# ESOL01_-_Sol_Pump.net
KiCad netlist of a schematic drawn in EAGLE
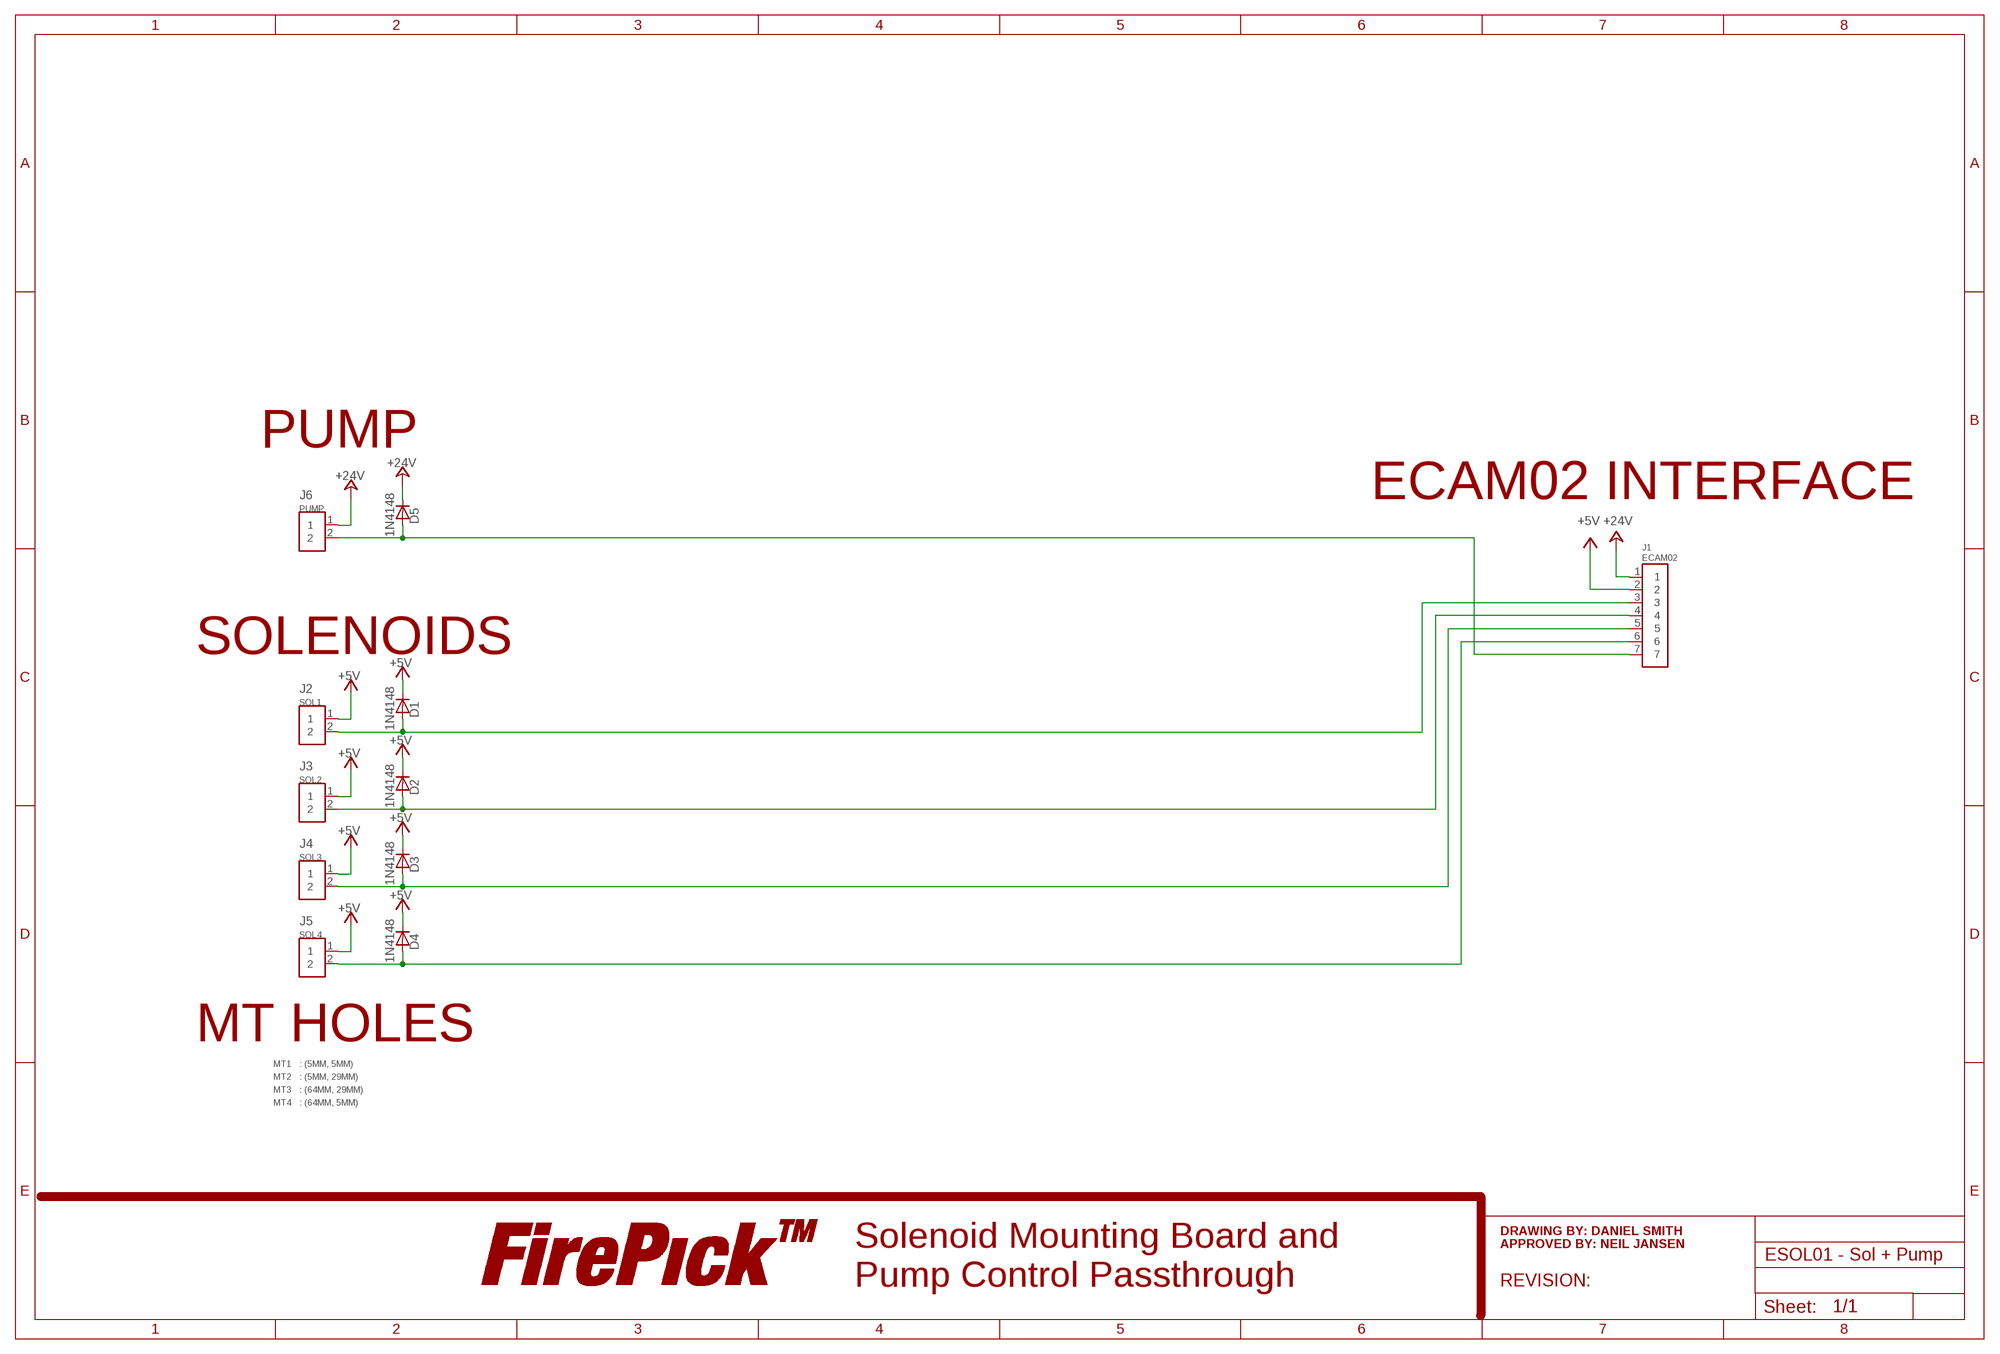
[diagram p0: schematic, sheet 1]

(export (version "E")
  (design (tool "Eeschema 10.0.6"))
  (components
    (comp (ref "D1")
      (value "1N4148")
      (footprint "eagle-import:SOD-323")
      (libsource (lib "eagle-import") (part "CPL-DIO-1N4148SOD-323"))
    )
    (comp (ref "D2")
      (value "1N4148")
      (footprint "eagle-import:SOD-323")
      (libsource (lib "eagle-import") (part "CPL-DIO-1N4148SOD-323"))
    )
    (comp (ref "D3")
      (value "1N4148")
      (footprint "eagle-import:SOD-323")
      (libsource (lib "eagle-import") (part "CPL-DIO-1N4148SOD-323"))
    )
    (comp (ref "D4")
      (value "1N4148")
      (footprint "eagle-import:SOD-323")
      (libsource (lib "eagle-import") (part "CPL-DIO-1N4148SOD-323"))
    )
    (comp (ref "D5")
      (value "1N4148")
      (footprint "eagle-import:SOD-323")
      (libsource (lib "eagle-import") (part "CPL-DIO-1N4148SOD-323"))
    )
    (comp (ref "J1")
      (value "ECAM02")
      (footprint "eagle-import:CON-JST-PH-2.0MM-7P-SMT-VRT")
      (libsource (lib "eagle-import") (part "CPL-CON-JST-2.0MM-7P-M-SMT-VRT"))
    )
    (comp (ref "J2")
      (value "SOL1")
      (footprint "eagle-import:HOLEX2")
      (libsource (lib "eagle-import") (part "HOLEX2"))
    )
    (comp (ref "J3")
      (value "SOL2")
      (footprint "eagle-import:HOLEX2")
      (libsource (lib "eagle-import") (part "HOLEX2"))
    )
    (comp (ref "J4")
      (value "SOL3")
      (footprint "eagle-import:HOLEX2")
      (libsource (lib "eagle-import") (part "HOLEX2"))
    )
    (comp (ref "J5")
      (value "SOL4")
      (footprint "eagle-import:HOLEX2")
      (libsource (lib "eagle-import") (part "HOLEX2"))
    )
    (comp (ref "J6")
      (value "PUMP")
      (footprint "eagle-import:CON-JST-PH-2.0MM-2P-SMT-VRT")
      (libsource (lib "eagle-import") (part "CPL-CON-JST-2.0MM-2P-M-SMT-VRT"))
    )
    (comp (ref "LOGO2")
      (value "LOGO-FIREPICKLARGE")
      (footprint "eagle-import:LOGO-FIREPICK")
      (libsource (lib "eagle-import") (part "LOGO-FIREPICKLARGE"))
    )
    (comp (ref "MT1")
      (value ": (5MM, 5MM)")
      (footprint "eagle-import:MTHOLE(M3)")
      (libsource (lib "eagle-import") (part "MTHOLE(M3)"))
    )
    (comp (ref "MT2")
      (value ": (5MM, 29MM)")
      (footprint "eagle-import:MTHOLE(M3)")
      (libsource (lib "eagle-import") (part "MTHOLE(M3)"))
    )
    (comp (ref "MT3")
      (value ": (64MM, 29MM)")
      (footprint "eagle-import:MTHOLE(M3)")
      (libsource (lib "eagle-import") (part "MTHOLE(M3)"))
    )
    (comp (ref "MT4")
      (value ": (64MM, 5MM)")
      (footprint "eagle-import:MTHOLE(M3)")
      (libsource (lib "eagle-import") (part "MTHOLE(M3)"))
    )
  )
  (nets
    (net (code "1") (name "+5V") (class "Default")
      (node (ref "D1") (pin "NEG") (pinfunction "C_NEG") (pintype "passive"))
      (node (ref "D2") (pin "NEG") (pinfunction "C_NEG") (pintype "passive"))
      (node (ref "D3") (pin "NEG") (pinfunction "C_NEG") (pintype "passive"))
      (node (ref "D4") (pin "NEG") (pinfunction "C_NEG") (pintype "passive"))
      (node (ref "J1") (pin "2") (pinfunction "2_2") (pintype "bidirectional"))
      (node (ref "J2") (pin "1") (pinfunction "1_1") (pintype "passive"))
      (node (ref "J3") (pin "1") (pinfunction "1_1") (pintype "passive"))
      (node (ref "J4") (pin "1") (pinfunction "1_1") (pintype "passive"))
      (node (ref "J5") (pin "1") (pinfunction "1_1") (pintype "passive"))
    )
    (net (code "2") (name "+24V") (class "Default")
      (node (ref "D5") (pin "NEG") (pinfunction "C_NEG") (pintype "passive"))
      (node (ref "J1") (pin "1") (pinfunction "1_1") (pintype "bidirectional"))
      (node (ref "J6") (pin "1") (pinfunction "1_1") (pintype "passive"))
    )
    (net (code "3") (name "Net-(D1-A)") (class "Default")
      (node (ref "D1") (pin "POS") (pinfunction "A_POS") (pintype "passive"))
      (node (ref "J1") (pin "3") (pinfunction "3_3") (pintype "bidirectional"))
      (node (ref "J2") (pin "2") (pinfunction "2_2") (pintype "passive"))
    )
    (net (code "4") (name "Net-(D2-A)") (class "Default")
      (node (ref "D2") (pin "POS") (pinfunction "A_POS") (pintype "passive"))
      (node (ref "J1") (pin "4") (pinfunction "4_4") (pintype "bidirectional"))
      (node (ref "J3") (pin "2") (pinfunction "2_2") (pintype "passive"))
    )
    (net (code "5") (name "Net-(D3-A)") (class "Default")
      (node (ref "D3") (pin "POS") (pinfunction "A_POS") (pintype "passive"))
      (node (ref "J1") (pin "5") (pinfunction "5_5") (pintype "bidirectional"))
      (node (ref "J4") (pin "2") (pinfunction "2_2") (pintype "passive"))
    )
    (net (code "6") (name "Net-(D4-A)") (class "Default")
      (node (ref "D4") (pin "POS") (pinfunction "A_POS") (pintype "passive"))
      (node (ref "J1") (pin "6") (pinfunction "6_6") (pintype "bidirectional"))
      (node (ref "J5") (pin "2") (pinfunction "2_2") (pintype "passive"))
    )
    (net (code "7") (name "Net-(D5-A)") (class "Default")
      (node (ref "D5") (pin "POS") (pinfunction "A_POS") (pintype "passive"))
      (node (ref "J1") (pin "7") (pinfunction "7_7") (pintype "bidirectional"))
      (node (ref "J6") (pin "2") (pinfunction "2_2") (pintype "passive"))
    )
  )
)
